# GPS.net
KiCad netlist of a schematic drawn in Altium Designer
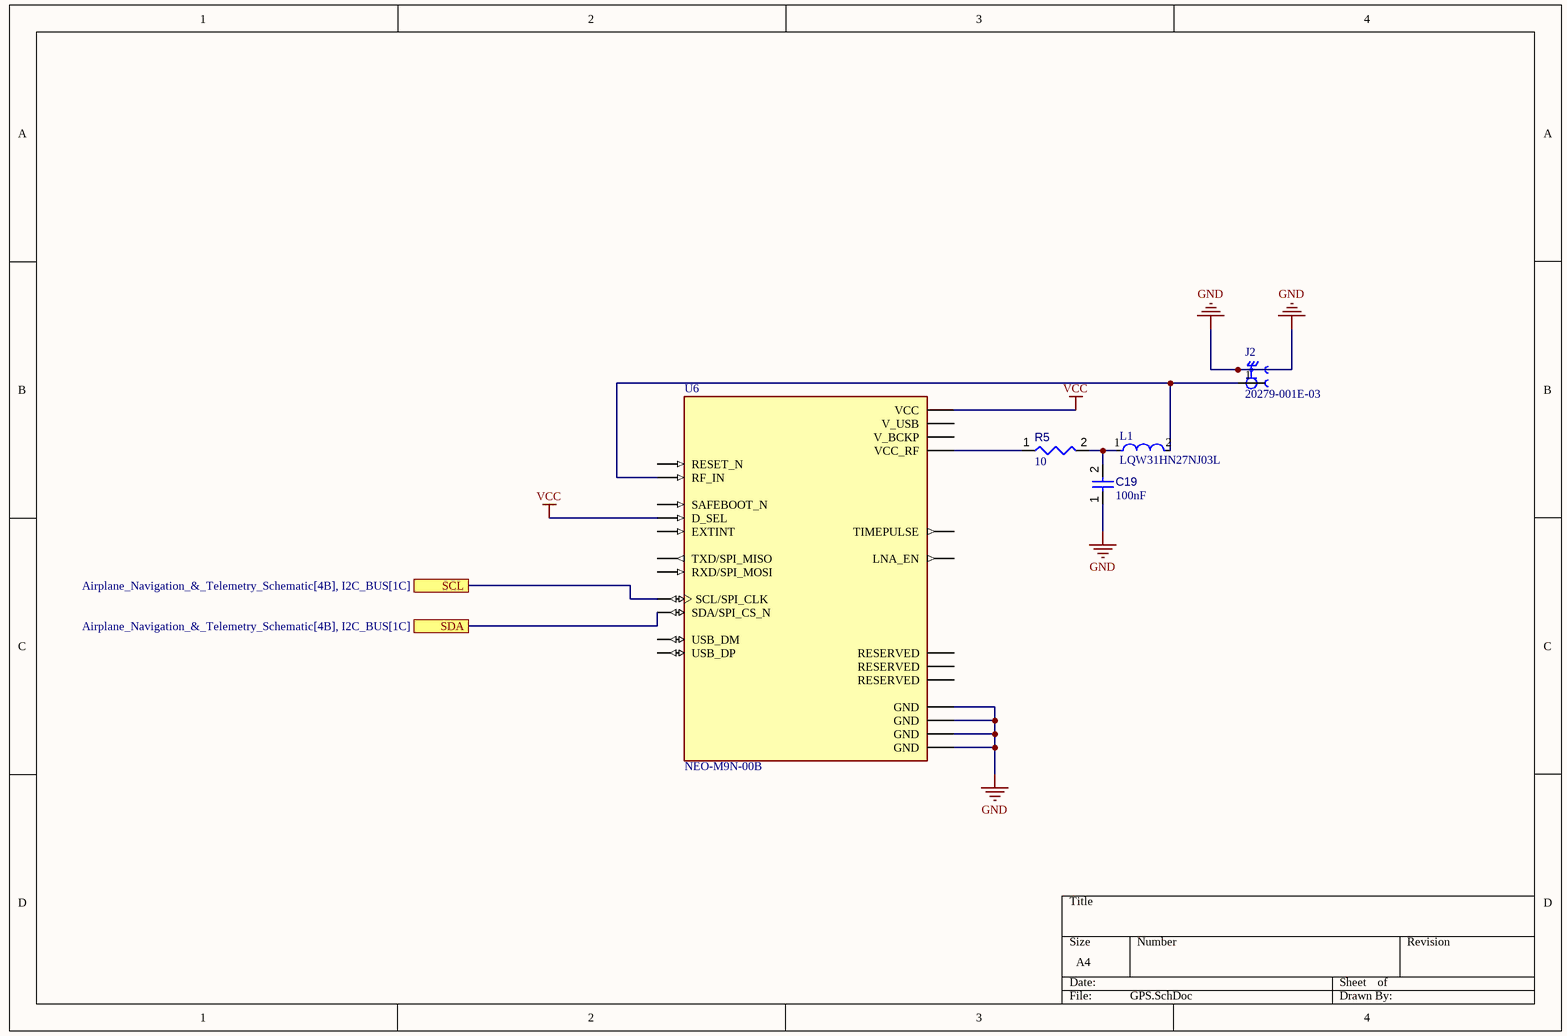
[diagram p0: GPS.SchDoc]

(export (version "E")
  (design (tool "Eeschema 10.0.6"))
  (components
    (comp (ref "C19")
      (value "100nF")
      (footprint "CAPC1608X90X40NL10T20")
      (description "Chip Capacitor, 100 nF, +/- 10%, 50 V, 0603 (1608 Metric)")
      (fields (field (name "TOLERANCE") "10%") (field (name "Comment") "Capacitor 100 nF +/-10% 50 V 0603"))
      (libsource (lib "Lachlan Biersteker") (part "CAP-NP-2"))
    )
    (comp (ref "J2")
      (value "20279-001E-03")
      (footprint "IPEX_20279-001E-03")
      (fields (field (name "MF") "I-PEX"))
      (libsource (lib "Lachlan Biersteker") (part "20279-001E-03"))
    )
    (comp (ref "L1")
      (value "LQW31HN27NJ03L")
      (footprint "FP-LQW31HN_03-MFG")
      (description "Wire Wound RF Inductor 27nH ±5% 0.0714Ω 560mA 1206")
      (fields (field (name "TOLERANCE") "5%"))
      (libsource (lib "Altium Content Vault") (part "725321dda6339637d4d059423bc1c3c"))
    )
    (comp (ref "R5")
      (value "10")
      (footprint "RESC0402(1005)_L")
      (description "Chip Resistor, 10 Ohms, +/-1 %, 63 mW, -55 to 155 degC, 0402")
      (fields (field (name "TOLERANCE") "1%") (field (name "POWER") "63mW"))
      (libsource (lib "Lachlan Biersteker") (part "RES-2"))
    )
    (comp (ref "U6")
      (value "NEO-M9N-00B")
      (footprint "XCVR_NEO-M9N-00B")
      (description "series RF Receiver BeiDou, Galileo, GLONASS, GNSS, GPS - -167dBm - - Module")
      (fields (field (name "MF") "u-blox"))
      (libsource (lib "Lachlan Biersteker") (part "NEO-M9N-00B"))
    )
  )
  (nets
    (net (code "1") (name "/SCL") (class "Default")
      (node (ref "U6") (pin "19") (pinfunction "SCL/SPI_CLK_19") (pintype "bidirectional"))
    )
    (net (code "2") (name "/SDA") (class "Default")
      (node (ref "U6") (pin "18") (pinfunction "SDA/SPI_CS_N_18") (pintype "bidirectional"))
    )
    (net (code "3") (name "GND") (class "Default")
      (node (ref "C19") (pin "1") (pinfunction "1_1") (pintype "passive"))
      (node (ref "J2") (pin "2") (pinfunction "GROUND_2") (pintype "passive"))
      (node (ref "J2") (pin "3") (pinfunction "GROUND_3") (pintype "passive"))
      (node (ref "U6") (pin "10") (pinfunction "GND_10") (pintype "power_in"))
      (node (ref "U6") (pin "12") (pinfunction "GND_12") (pintype "power_in"))
      (node (ref "U6") (pin "13") (pinfunction "GND_13") (pintype "power_in"))
      (node (ref "U6") (pin "24") (pinfunction "GND_24") (pintype "power_in"))
    )
    (net (code "4") (name "Net-(C19-Pad2)") (class "Default")
      (node (ref "C19") (pin "2") (pinfunction "2_2") (pintype "passive"))
      (node (ref "L1") (pin "1") (pinfunction "1_1") (pintype "passive"))
      (node (ref "R5") (pin "2") (pinfunction "2_2") (pintype "passive"))
    )
    (net (code "5") (name "Net-(J2-SIGNAL)") (class "Default")
      (node (ref "J2") (pin "1") (pinfunction "SIGNAL_1") (pintype "passive"))
      (node (ref "L1") (pin "2") (pinfunction "2_2") (pintype "passive"))
      (node (ref "U6") (pin "11") (pinfunction "RF_IN_11") (pintype "input"))
    )
    (net (code "6") (name "Net-(U6-VCC_RF)") (class "Default")
      (node (ref "R5") (pin "1") (pinfunction "1_1") (pintype "passive"))
      (node (ref "U6") (pin "9") (pinfunction "VCC_RF_9") (pintype "power_in"))
    )
    (net (code "7") (name "VCC") (class "Default")
      (node (ref "U6") (pin "2") (pinfunction "D_SEL_2") (pintype "input"))
      (node (ref "U6") (pin "23") (pinfunction "VCC_23") (pintype "power_in"))
    )
    (net (code "8") (name "unconnected-(U6-EXTINT-Pad4)") (class "Default")
      (node (ref "U6") (pin "4") (pinfunction "EXTINT_4") (pintype "input"))
    )
    (net (code "9") (name "unconnected-(U6-LNA_EN-Pad14)") (class "Default")
      (node (ref "U6") (pin "14") (pinfunction "LNA_EN_14") (pintype "output"))
    )
    (net (code "10") (name "unconnected-(U6-RESERVED-Pad15)") (class "Default")
      (node (ref "U6") (pin "15") (pinfunction "RESERVED_15") (pintype "passive"))
    )
    (net (code "11") (name "unconnected-(U6-RESERVED-Pad16)") (class "Default")
      (node (ref "U6") (pin "16") (pinfunction "RESERVED_16") (pintype "passive"))
    )
    (net (code "12") (name "unconnected-(U6-RESERVED-Pad17)") (class "Default")
      (node (ref "U6") (pin "17") (pinfunction "RESERVED_17") (pintype "passive"))
    )
    (net (code "13") (name "unconnected-(U6-RESET_N-Pad8)") (class "Default")
      (node (ref "U6") (pin "8") (pinfunction "RESET_N_8") (pintype "input"))
    )
    (net (code "14") (name "unconnected-(U6-RXD{slash}SPI_MOSI-Pad21)") (class "Default")
      (node (ref "U6") (pin "21") (pinfunction "RXD/SPI_MOSI_21") (pintype "input"))
    )
    (net (code "15") (name "unconnected-(U6-SAFEBOOT_N-Pad1)") (class "Default")
      (node (ref "U6") (pin "1") (pinfunction "SAFEBOOT_N_1") (pintype "input"))
    )
    (net (code "16") (name "unconnected-(U6-TIMEPULSE-Pad3)") (class "Default")
      (node (ref "U6") (pin "3") (pinfunction "TIMEPULSE_3") (pintype "output"))
    )
    (net (code "17") (name "unconnected-(U6-TXD{slash}SPI_MISO-Pad20)") (class "Default")
      (node (ref "U6") (pin "20") (pinfunction "TXD/SPI_MISO_20") (pintype "output"))
    )
    (net (code "18") (name "unconnected-(U6-USB_DM-Pad5)") (class "Default")
      (node (ref "U6") (pin "5") (pinfunction "USB_DM_5") (pintype "bidirectional"))
    )
    (net (code "19") (name "unconnected-(U6-USB_DP-Pad6)") (class "Default")
      (node (ref "U6") (pin "6") (pinfunction "USB_DP_6") (pintype "bidirectional"))
    )
    (net (code "20") (name "unconnected-(U6-V_BCKP-Pad22)") (class "Default")
      (node (ref "U6") (pin "22") (pinfunction "V_BCKP_22") (pintype "power_in"))
    )
    (net (code "21") (name "unconnected-(U6-V_USB-Pad7)") (class "Default")
      (node (ref "U6") (pin "7") (pinfunction "V_USB_7") (pintype "power_in"))
    )
  )
)
